# Przelacznik.net
KiCad netlist of a schematic drawn in EAGLE
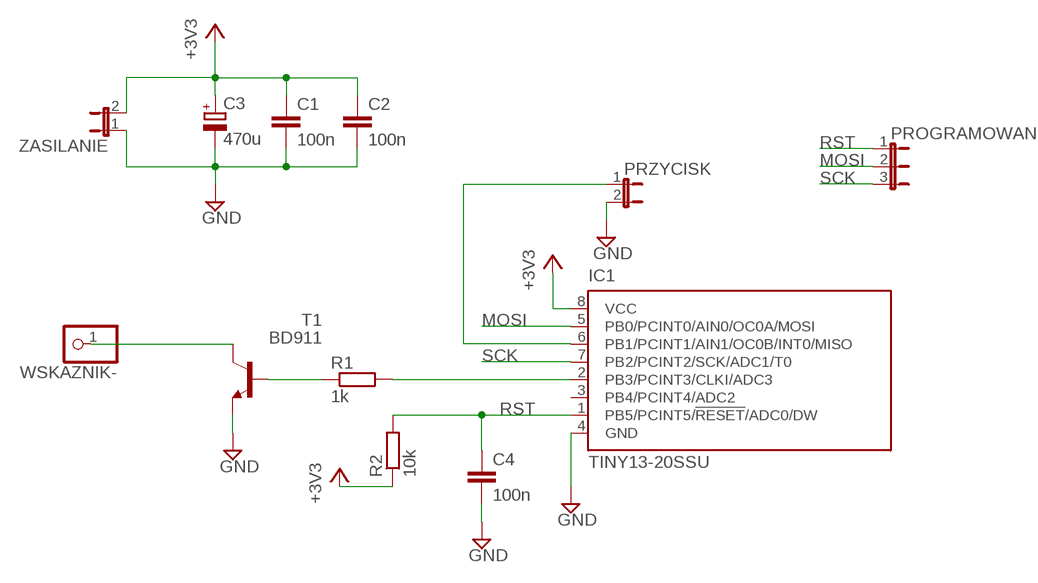
[diagram p0: schematic, sheet 1]

(export (version "E")
  (design (tool "Eeschema 10.0.6"))
  (components
    (comp (ref "C1")
      (value "100n")
      (footprint "eagle-import:C025-024X044")
      (libsource (lib "eagle-import") (part "C-EU025-024X044"))
    )
    (comp (ref "C2")
      (value "100n")
      (footprint "eagle-import:C0805")
      (libsource (lib "eagle-import") (part "C-EUC0805"))
    )
    (comp (ref "C3")
      (value "470u")
      (footprint "eagle-import:E3,5-8")
      (libsource (lib "eagle-import") (part "CPOL-EUE3.5-8"))
    )
    (comp (ref "C4")
      (value "100n")
      (footprint "eagle-import:C025-024X044")
      (libsource (lib "eagle-import") (part "C-EU025-024X044"))
    )
    (comp (ref "IC1")
      (value "TINY13-20SSU")
      (footprint "eagle-import:8S1")
      (fields (field (name "MPN") "ATTINY13-20SSU"))
      (libsource (lib "eagle-import") (part "TINY13SSU-20"))
    )
    (comp (ref "PROGRAMOWANIE")
      (value "JP2E")
      (footprint "eagle-import:JP2")
      (libsource (lib "eagle-import") (part "JP2E"))
    )
    (comp (ref "PRZYCISK")
      (value "JP1E")
      (footprint "eagle-import:JP1")
      (libsource (lib "eagle-import") (part "JP1E"))
    )
    (comp (ref "R1")
      (value "1k")
      (footprint "eagle-import:0411_12")
      (libsource (lib "eagle-import") (part "R-EU_0411/12"))
    )
    (comp (ref "R2")
      (value "10k")
      (footprint "eagle-import:0411_12")
      (libsource (lib "eagle-import") (part "R-EU_0411/12"))
    )
    (comp (ref "T1")
      (value "BD911")
      (footprint "eagle-import:TO220")
      (libsource (lib "eagle-import") (part "-NPN-TO220"))
    )
    (comp (ref "WSKAZNIK-")
      (value "PINHD-1X1")
      (footprint "eagle-import:1X01")
      (libsource (lib "eagle-import") (part "PINHD-1X1"))
    )
    (comp (ref "ZASILANIE")
      (value "JP1E")
      (footprint "eagle-import:JP1")
      (libsource (lib "eagle-import") (part "JP1E"))
    )
  )
  (nets
    (net (code "1") (name "+3V3") (class "Default")
      (node (ref "C1") (pin "1") (pinfunction "1_1") (pintype "passive"))
      (node (ref "C2") (pin "1") (pinfunction "1_1") (pintype "passive"))
      (node (ref "C3") (pin "+") (pinfunction "+_+") (pintype "passive"))
      (node (ref "IC1") (pin "8") (pinfunction "VCC_8") (pintype "power_in"))
      (node (ref "R2") (pin "1") (pinfunction "1_1") (pintype "passive"))
      (node (ref "ZASILANIE") (pin "2") (pinfunction "2_2") (pintype "passive"))
    )
    (net (code "2") (name "/MOSI") (class "Default")
      (node (ref "IC1") (pin "5") (pinfunction "PB0/PCINT0/AIN0/OC0A/MOSI_5") (pintype "bidirectional"))
      (node (ref "PROGRAMOWANIE") (pin "2") (pinfunction "2_2") (pintype "passive"))
    )
    (net (code "3") (name "/RST") (class "Default")
      (node (ref "C4") (pin "1") (pinfunction "1_1") (pintype "passive"))
      (node (ref "IC1") (pin "1") (pinfunction "PB5/PCINT5/~{RESET}/ADC0/DW_1") (pintype "bidirectional"))
      (node (ref "PROGRAMOWANIE") (pin "1") (pinfunction "1_1") (pintype "passive"))
      (node (ref "R2") (pin "2") (pinfunction "2_2") (pintype "passive"))
    )
    (net (code "4") (name "/SCK") (class "Default")
      (node (ref "IC1") (pin "7") (pinfunction "PB2/PCINT2/SCK/ADC1/T0_7") (pintype "bidirectional"))
      (node (ref "PROGRAMOWANIE") (pin "3") (pinfunction "3_3") (pintype "passive"))
    )
    (net (code "5") (name "GND") (class "Default")
      (node (ref "C1") (pin "2") (pinfunction "2_2") (pintype "passive"))
      (node (ref "C2") (pin "2") (pinfunction "2_2") (pintype "passive"))
      (node (ref "C3") (pin "-") (pinfunction "-_-") (pintype "passive"))
      (node (ref "C4") (pin "2") (pinfunction "2_2") (pintype "passive"))
      (node (ref "IC1") (pin "4") (pinfunction "GND_4") (pintype "power_in"))
      (node (ref "PRZYCISK") (pin "2") (pinfunction "2_2") (pintype "passive"))
      (node (ref "T1") (pin "3") (pinfunction "E_3") (pintype "passive"))
      (node (ref "ZASILANIE") (pin "1") (pinfunction "1_1") (pintype "passive"))
    )
    (net (code "6") (name "Net-(IC1-PB1{slash}PCINT1{slash}AIN1{slash}OC0B{slash}INT0{slash}MISO)") (class "Default")
      (node (ref "IC1") (pin "6") (pinfunction "PB1/PCINT1/AIN1/OC0B/INT0/MISO_6") (pintype "bidirectional"))
      (node (ref "PRZYCISK") (pin "1") (pinfunction "1_1") (pintype "passive"))
    )
    (net (code "7") (name "Net-(IC1-PB3{slash}PCINT3{slash}CLKI{slash}ADC3)") (class "Default")
      (node (ref "IC1") (pin "2") (pinfunction "PB3/PCINT3/CLKI/ADC3_2") (pintype "bidirectional"))
      (node (ref "R1") (pin "2") (pinfunction "2_2") (pintype "passive"))
    )
    (net (code "8") (name "Net-(T1-B)") (class "Default")
      (node (ref "R1") (pin "1") (pinfunction "1_1") (pintype "passive"))
      (node (ref "T1") (pin "1") (pinfunction "B_1") (pintype "passive"))
    )
    (net (code "9") (name "Net-(T1-C)") (class "Default")
      (node (ref "T1") (pin "2") (pinfunction "C_2") (pintype "passive"))
      (node (ref "WSKAZNIK-") (pin "1") (pinfunction "1_1") (pintype "passive"))
    )
    (net (code "10") (name "unconnected-(IC1-PB4{slash}PCINT4{slash}ADC2-Pad3)") (class "Default")
      (node (ref "IC1") (pin "3") (pinfunction "PB4/PCINT4/ADC2_3") (pintype "bidirectional"))
    )
  )
)
